# Parkingsensor.net
KiCad netlist of a schematic drawn in EAGLE
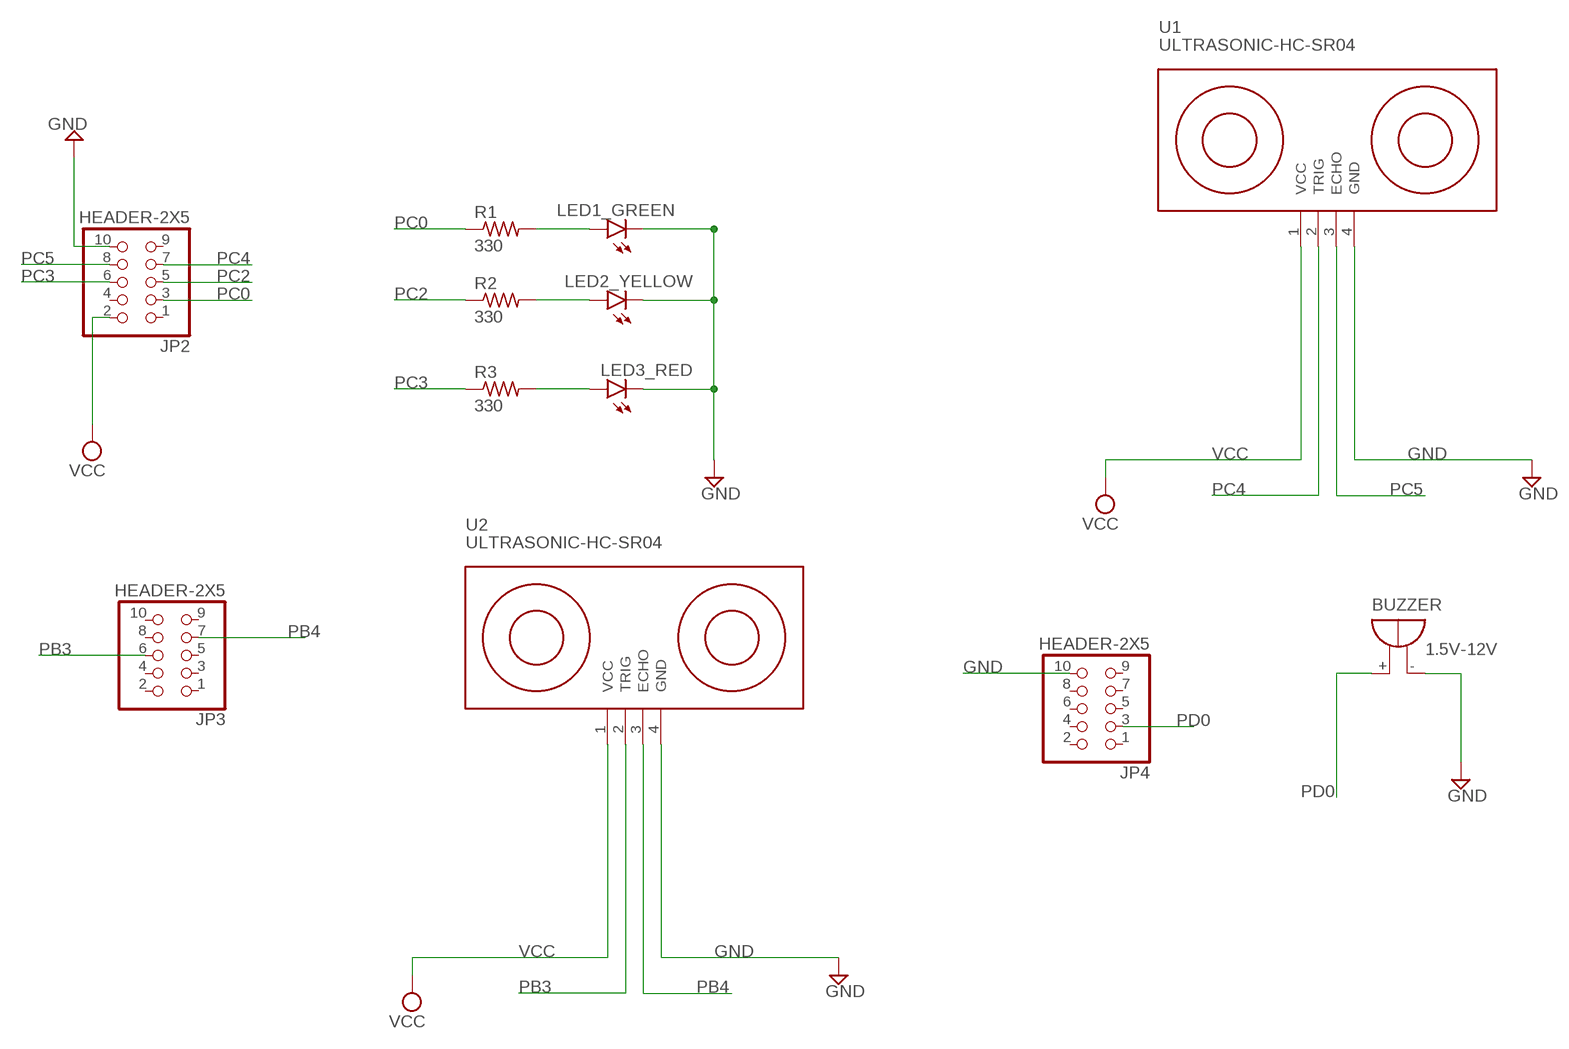
[diagram p0: schematic, sheet 1]

(export (version "E")
  (design (tool "Eeschema 10.0.6"))
  (components
    (comp (ref "BUZZER")
      (value "1.5V-12V")
      (footprint "eagle-import:EB2209A")
      (libsource (lib "eagle-import") (part "EB2209A"))
    )
    (comp (ref "JP2")
      (value "HEADER-2X5")
      (footprint "eagle-import:2X05")
      (libsource (lib "eagle-import") (part "HEADER-2X5"))
    )
    (comp (ref "JP3")
      (value "HEADER-2X5")
      (footprint "eagle-import:2X05")
      (libsource (lib "eagle-import") (part "HEADER-2X5"))
    )
    (comp (ref "JP4")
      (value "HEADER-2X5")
      (footprint "eagle-import:2X05")
      (libsource (lib "eagle-import") (part "HEADER-2X5"))
    )
    (comp (ref "LED1_GREEN")
      (value "LED3MM")
      (footprint "eagle-import:LED3MM")
      (libsource (lib "eagle-import") (part "LED3MM"))
    )
    (comp (ref "LED2_YELLOW")
      (value "LED3MM")
      (footprint "eagle-import:LED3MM")
      (libsource (lib "eagle-import") (part "LED3MM"))
    )
    (comp (ref "LED3_RED")
      (value "LED3MM")
      (footprint "eagle-import:LED3MM")
      (libsource (lib "eagle-import") (part "LED3MM"))
    )
    (comp (ref "R1")
      (value "330")
      (footprint "eagle-import:0207_10")
      (libsource (lib "eagle-import") (part "R-US_0207/10"))
    )
    (comp (ref "R2")
      (value "330")
      (footprint "eagle-import:0207_10")
      (libsource (lib "eagle-import") (part "R-US_0207/10"))
    )
    (comp (ref "R3")
      (value "330")
      (footprint "eagle-import:0207_10")
      (libsource (lib "eagle-import") (part "R-US_0207/10"))
    )
    (comp (ref "U1")
      (value "ULTRASONIC-HC-SR04")
      (footprint "eagle-import:ULTRASONIC-HC-SR04")
      (libsource (lib "eagle-import") (part "ULTRASONIC-HC-SR04"))
    )
    (comp (ref "U2")
      (value "ULTRASONIC-HC-SR04")
      (footprint "eagle-import:ULTRASONIC-HC-SR04")
      (libsource (lib "eagle-import") (part "ULTRASONIC-HC-SR04"))
    )
  )
  (nets
    (net (code "1") (name "/PB3") (class "Default")
      (node (ref "JP3") (pin "6") (pinfunction "6_6") (pintype "passive"))
      (node (ref "U2") (pin "2") (pinfunction "TRIG_2") (pintype "input"))
    )
    (net (code "2") (name "/PB4") (class "Default")
      (node (ref "JP3") (pin "7") (pinfunction "7_7") (pintype "passive"))
      (node (ref "U2") (pin "3") (pinfunction "ECHO_3") (pintype "output"))
    )
    (net (code "3") (name "/PC0") (class "Default")
      (node (ref "JP2") (pin "3") (pinfunction "3_3") (pintype "passive"))
      (node (ref "R1") (pin "1") (pinfunction "1_1") (pintype "passive"))
    )
    (net (code "4") (name "/PC2") (class "Default")
      (node (ref "JP2") (pin "5") (pinfunction "5_5") (pintype "passive"))
      (node (ref "R2") (pin "1") (pinfunction "1_1") (pintype "passive"))
    )
    (net (code "5") (name "/PC3") (class "Default")
      (node (ref "JP2") (pin "6") (pinfunction "6_6") (pintype "passive"))
      (node (ref "R3") (pin "1") (pinfunction "1_1") (pintype "passive"))
    )
    (net (code "6") (name "/PC4") (class "Default")
      (node (ref "JP2") (pin "7") (pinfunction "7_7") (pintype "passive"))
      (node (ref "U1") (pin "2") (pinfunction "TRIG_2") (pintype "input"))
    )
    (net (code "7") (name "/PC5") (class "Default")
      (node (ref "JP2") (pin "8") (pinfunction "8_8") (pintype "passive"))
      (node (ref "U1") (pin "3") (pinfunction "ECHO_3") (pintype "output"))
    )
    (net (code "8") (name "/PD0") (class "Default")
      (node (ref "BUZZER") (pin "+") (pinfunction "+_+") (pintype "passive"))
      (node (ref "JP4") (pin "3") (pinfunction "3_3") (pintype "passive"))
    )
    (net (code "9") (name "GND") (class "Default")
      (node (ref "BUZZER") (pin "-") (pinfunction "-_-") (pintype "passive"))
      (node (ref "JP2") (pin "10") (pinfunction "10_10") (pintype "passive"))
      (node (ref "JP4") (pin "10") (pinfunction "10_10") (pintype "passive"))
      (node (ref "LED1_GREEN") (pin "K") (pinfunction "C_K") (pintype "passive"))
      (node (ref "LED2_YELLOW") (pin "K") (pinfunction "C_K") (pintype "passive"))
      (node (ref "LED3_RED") (pin "K") (pinfunction "C_K") (pintype "passive"))
      (node (ref "U1") (pin "4") (pinfunction "GND_4") (pintype "power_in"))
      (node (ref "U2") (pin "4") (pinfunction "GND_4") (pintype "power_in"))
    )
    (net (code "10") (name "Net-(LED1_GREEN-PadA)") (class "Default")
      (node (ref "LED1_GREEN") (pin "A") (pinfunction "A_A") (pintype "passive"))
      (node (ref "R1") (pin "2") (pinfunction "2_2") (pintype "passive"))
    )
    (net (code "11") (name "Net-(LED2_YELLOW-PadA)") (class "Default")
      (node (ref "LED2_YELLOW") (pin "A") (pinfunction "A_A") (pintype "passive"))
      (node (ref "R2") (pin "2") (pinfunction "2_2") (pintype "passive"))
    )
    (net (code "12") (name "Net-(LED3_RED-PadA)") (class "Default")
      (node (ref "LED3_RED") (pin "A") (pinfunction "A_A") (pintype "passive"))
      (node (ref "R3") (pin "2") (pinfunction "2_2") (pintype "passive"))
    )
    (net (code "13") (name "VCC") (class "Default")
      (node (ref "JP2") (pin "2") (pinfunction "2_2") (pintype "passive"))
      (node (ref "U1") (pin "1") (pinfunction "VCC_1") (pintype "power_in"))
      (node (ref "U2") (pin "1") (pinfunction "VCC_1") (pintype "power_in"))
    )
    (net (code "14") (name "unconnected-(JP2-Pad1)") (class "Default")
      (node (ref "JP2") (pin "1") (pinfunction "1_1") (pintype "passive"))
    )
    (net (code "15") (name "unconnected-(JP2-Pad4)") (class "Default")
      (node (ref "JP2") (pin "4") (pinfunction "4_4") (pintype "passive"))
    )
    (net (code "16") (name "unconnected-(JP2-Pad9)") (class "Default")
      (node (ref "JP2") (pin "9") (pinfunction "9_9") (pintype "passive"))
    )
    (net (code "17") (name "unconnected-(JP3-Pad1)") (class "Default")
      (node (ref "JP3") (pin "1") (pinfunction "1_1") (pintype "passive"))
    )
    (net (code "18") (name "unconnected-(JP3-Pad2)") (class "Default")
      (node (ref "JP3") (pin "2") (pinfunction "2_2") (pintype "passive"))
    )
    (net (code "19") (name "unconnected-(JP3-Pad3)") (class "Default")
      (node (ref "JP3") (pin "3") (pinfunction "3_3") (pintype "passive"))
    )
    (net (code "20") (name "unconnected-(JP3-Pad4)") (class "Default")
      (node (ref "JP3") (pin "4") (pinfunction "4_4") (pintype "passive"))
    )
    (net (code "21") (name "unconnected-(JP3-Pad5)") (class "Default")
      (node (ref "JP3") (pin "5") (pinfunction "5_5") (pintype "passive"))
    )
    (net (code "22") (name "unconnected-(JP3-Pad8)") (class "Default")
      (node (ref "JP3") (pin "8") (pinfunction "8_8") (pintype "passive"))
    )
    (net (code "23") (name "unconnected-(JP3-Pad9)") (class "Default")
      (node (ref "JP3") (pin "9") (pinfunction "9_9") (pintype "passive"))
    )
    (net (code "24") (name "unconnected-(JP3-Pad10)") (class "Default")
      (node (ref "JP3") (pin "10") (pinfunction "10_10") (pintype "passive"))
    )
    (net (code "25") (name "unconnected-(JP4-Pad1)") (class "Default")
      (node (ref "JP4") (pin "1") (pinfunction "1_1") (pintype "passive"))
    )
    (net (code "26") (name "unconnected-(JP4-Pad2)") (class "Default")
      (node (ref "JP4") (pin "2") (pinfunction "2_2") (pintype "passive"))
    )
    (net (code "27") (name "unconnected-(JP4-Pad4)") (class "Default")
      (node (ref "JP4") (pin "4") (pinfunction "4_4") (pintype "passive"))
    )
    (net (code "28") (name "unconnected-(JP4-Pad5)") (class "Default")
      (node (ref "JP4") (pin "5") (pinfunction "5_5") (pintype "passive"))
    )
    (net (code "29") (name "unconnected-(JP4-Pad6)") (class "Default")
      (node (ref "JP4") (pin "6") (pinfunction "6_6") (pintype "passive"))
    )
    (net (code "30") (name "unconnected-(JP4-Pad7)") (class "Default")
      (node (ref "JP4") (pin "7") (pinfunction "7_7") (pintype "passive"))
    )
    (net (code "31") (name "unconnected-(JP4-Pad8)") (class "Default")
      (node (ref "JP4") (pin "8") (pinfunction "8_8") (pintype "passive"))
    )
    (net (code "32") (name "unconnected-(JP4-Pad9)") (class "Default")
      (node (ref "JP4") (pin "9") (pinfunction "9_9") (pintype "passive"))
    )
  )
)
